# M12_Part_Left.net
KiCad netlist of a schematic drawn in Altium Designer
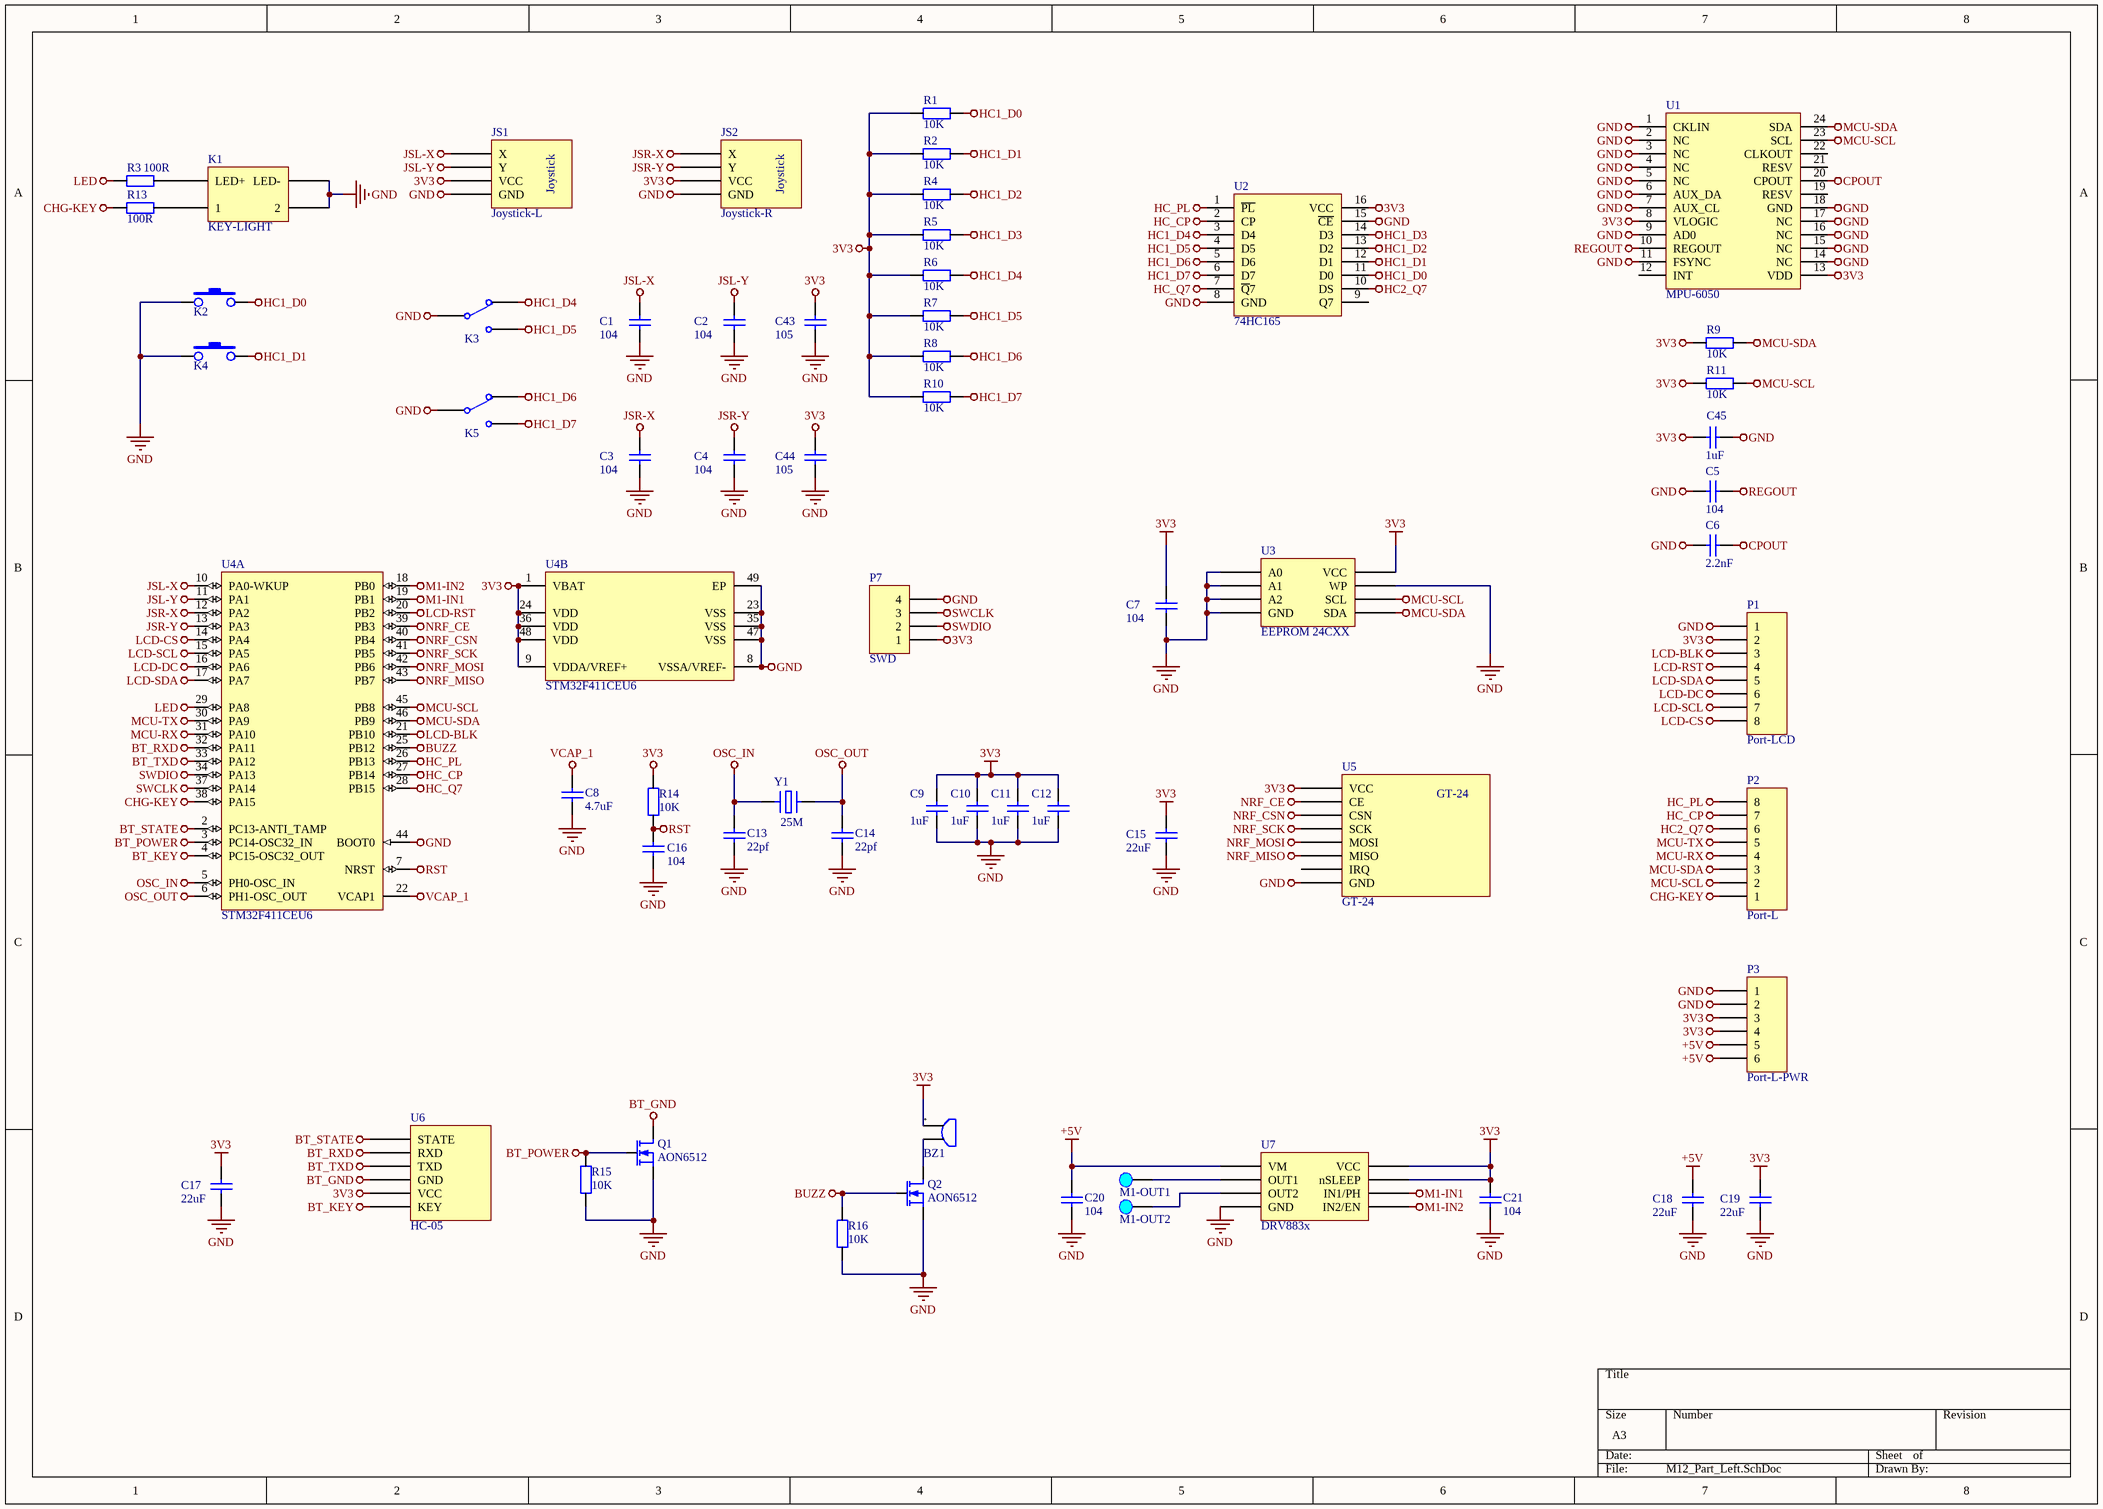
[diagram p0: M12_Part_Left.SchDoc]

(export (version "E")
  (design (tool "Eeschema 10.0.6"))
  (components
    (comp (ref "BZ1")
      (value "蜂鸣器")
      (footprint "BUZ-SMD_4P-L7.5-W7.5-P7.59-BR")
      (libsource (lib "元件库") (part "BZ"))
    )
    (comp (ref "C1")
      (value "104")
      (footprint "电容_C0603")
      (fields (field (name "C") "104"))
      (libsource (lib "元件库") (part "cap"))
    )
    (comp (ref "C2")
      (value "104")
      (footprint "电容_C0603")
      (fields (field (name "C") "104"))
      (libsource (lib "元件库") (part "cap"))
    )
    (comp (ref "C3")
      (value "104")
      (footprint "电容_C0603")
      (fields (field (name "C") "104"))
      (libsource (lib "元件库") (part "cap"))
    )
    (comp (ref "C4")
      (value "104")
      (footprint "电容_C0603")
      (fields (field (name "C") "104"))
      (libsource (lib "元件库") (part "cap"))
    )
    (comp (ref "C5")
      (value "104")
      (footprint "电容_C0603")
      (fields (field (name "C") "104"))
      (libsource (lib "元件库") (part "cap"))
    )
    (comp (ref "C6")
      (value "2.2nF")
      (footprint "电容_C0603")
      (fields (field (name "C") "2.2nF"))
      (libsource (lib "元件库") (part "cap"))
    )
    (comp (ref "C7")
      (value "104")
      (footprint "电容_C0603")
      (fields (field (name "C") "104"))
      (libsource (lib "元件库") (part "cap"))
    )
    (comp (ref "C8")
      (value "4.7uF")
      (footprint "电容_C0603")
      (fields (field (name "C") "4.7uF"))
      (libsource (lib "元件库") (part "cap"))
    )
    (comp (ref "C9")
      (value "1uF")
      (footprint "电容_C0603")
      (fields (field (name "C") "1uF"))
      (libsource (lib "元件库") (part "cap"))
    )
    (comp (ref "C10")
      (value "1uF")
      (footprint "电容_C0603")
      (fields (field (name "C") "1uF"))
      (libsource (lib "元件库") (part "cap"))
    )
    (comp (ref "C11")
      (value "1uF")
      (footprint "电容_C0603")
      (fields (field (name "C") "1uF"))
      (libsource (lib "元件库") (part "cap"))
    )
    (comp (ref "C12")
      (value "1uF")
      (footprint "电容_C0603")
      (fields (field (name "C") "1uF"))
      (libsource (lib "元件库") (part "cap"))
    )
    (comp (ref "C13")
      (value "22pf")
      (footprint "电容_C0603")
      (fields (field (name "C") "22pf"))
      (libsource (lib "元件库") (part "cap"))
    )
    (comp (ref "C14")
      (value "22pf")
      (footprint "电容_C0603")
      (fields (field (name "C") "22pf"))
      (libsource (lib "元件库") (part "cap"))
    )
    (comp (ref "C15")
      (value "22uF")
      (footprint "电容_C1206")
      (fields (field (name "C") "22uF"))
      (libsource (lib "元件库") (part "cap"))
    )
    (comp (ref "C16")
      (value "104")
      (footprint "电容_C0603")
      (fields (field (name "C") "104"))
      (libsource (lib "元件库") (part "cap"))
    )
    (comp (ref "C17")
      (value "22uF")
      (footprint "电容_C1206")
      (fields (field (name "C") "22uF"))
      (libsource (lib "元件库") (part "cap"))
    )
    (comp (ref "C18")
      (value "22uF")
      (footprint "电容_C1206")
      (fields (field (name "C") "22uF"))
      (libsource (lib "元件库") (part "cap"))
    )
    (comp (ref "C19")
      (value "22uF")
      (footprint "电容_C1206")
      (fields (field (name "C") "22uF"))
      (libsource (lib "元件库") (part "cap"))
    )
    (comp (ref "C20")
      (value "104")
      (footprint "电容_C0603")
      (fields (field (name "C") "104"))
      (libsource (lib "元件库") (part "cap"))
    )
    (comp (ref "C21")
      (value "104")
      (footprint "电容_C0603")
      (fields (field (name "C") "104"))
      (libsource (lib "元件库") (part "cap"))
    )
    (comp (ref "C43")
      (value "105")
      (footprint "电容_C0603")
      (fields (field (name "C") "105"))
      (libsource (lib "元件库") (part "cap"))
    )
    (comp (ref "C44")
      (value "105")
      (footprint "电容_C0603")
      (fields (field (name "C") "105"))
      (libsource (lib "元件库") (part "cap"))
    )
    (comp (ref "C45")
      (value "1uF")
      (footprint "电容_C0603")
      (fields (field (name "C") "1uF"))
      (libsource (lib "元件库") (part "cap"))
    )
    (comp (ref "JS1")
      (value "Joystick-L")
      (footprint "ZH1.5-LS-4P")
      (libsource (lib "xSchlib") (part "Joystick"))
    )
    (comp (ref "JS2")
      (value "Joystick-R")
      (footprint "ZH1.5-LS-4P")
      (libsource (lib "xSchlib") (part "Joystick"))
    )
    (comp (ref "K1")
      (value "KEY-LIGHT")
      (footprint "SW-TH_4P-L12.0-W12.0-P5.00-LS12.5")
      (libsource (lib "xSchlib") (part "KEY-LIGHT"))
    )
    (comp (ref "K2")
      (value "SKRP")
      (footprint "KEY-SMD_4P-L6.0-W6.0-P3.90-LS10.0")
      (libsource (lib "元件库") (part "SW-PB"))
    )
    (comp (ref "K3") (value "*") (footprint "ZH1.5-WS-3P") (libsource (lib "元件库") (part "KEY-3")))
    (comp (ref "K4")
      (value "SKRP")
      (footprint "KEY-SMD_4P-L6.0-W6.0-P3.90-LS10.0")
      (libsource (lib "元件库") (part "SW-PB"))
    )
    (comp (ref "K5") (value "*") (footprint "ZH1.5-WS-3P") (libsource (lib "元件库") (part "KEY-3")))
    (comp (ref "M1")
      (value "M1-OUT1")
      (footprint "Pad_B")
      (fields (field (name "_REMARKS") "M1-OUT1"))
      (libsource (lib "元件库") (part "Pad"))
    )
    (comp (ref "M2")
      (value "M1-OUT2")
      (footprint "Pad_B")
      (fields (field (name "_REMARKS") "M1-OUT2"))
      (libsource (lib "元件库") (part "Pad"))
    )
    (comp (ref "P1")
      (value "Port-LCD")
      (footprint "ZH1.5-LS-8P")
      (description "Header, 8-Pin")
      (fields (field (name "PUBLISHER") "Altium Limited"))
      (libsource (lib "") (part "Header 8_1"))
    )
    (comp (ref "P2")
      (value "Port-L")
      (footprint "ZH1.5-WS-8P")
      (description "Header, 8-Pin")
      (fields (field (name "PUBLISHER") "Altium Limited"))
      (libsource (lib "Miscellaneous Connectors") (part "Header 8"))
    )
    (comp (ref "P3")
      (value "Port-L-PWR")
      (footprint "ZH1.5-WS-6P")
      (description "Header, 6-Pin")
      (fields (field (name "PUBLISHER") "Altium Limited"))
      (libsource (lib "Miscellaneous Connectors") (part "Header 6"))
    )
    (comp (ref "P7")
      (value "SWD")
      (footprint "HDR1X4")
      (description "Header, 4-Pin")
      (fields (field (name "PUBLISHER") "Altium Limited"))
      (libsource (lib "Miscellaneous Connectors") (part "Header 4"))
    )
    (comp (ref "Q1") (value "AON6512") (footprint "MOS_SOT-23") (libsource (lib "元件库") (part "MOSFET-N")))
    (comp (ref "Q2") (value "AON6512") (footprint "MOS_SOT-23") (libsource (lib "元件库") (part "MOSFET-N")))
    (comp (ref "R1")
      (value "10K")
      (footprint "电阻_R0603")
      (fields (field (name "R") "10K"))
      (libsource (lib "元件库") (part "Res"))
    )
    (comp (ref "R2")
      (value "10K")
      (footprint "电阻_R0603")
      (fields (field (name "R") "10K"))
      (libsource (lib "元件库") (part "Res"))
    )
    (comp (ref "R3")
      (value "100R")
      (footprint "电阻_R0603")
      (fields (field (name "R") "100R"))
      (libsource (lib "元件库") (part "Res"))
    )
    (comp (ref "R4")
      (value "10K")
      (footprint "电阻_R0603")
      (fields (field (name "R") "10K"))
      (libsource (lib "元件库") (part "Res"))
    )
    (comp (ref "R5")
      (value "10K")
      (footprint "电阻_R0603")
      (fields (field (name "R") "10K"))
      (libsource (lib "元件库") (part "Res"))
    )
    (comp (ref "R6")
      (value "10K")
      (footprint "电阻_R0603")
      (fields (field (name "R") "10K"))
      (libsource (lib "元件库") (part "Res"))
    )
    (comp (ref "R7")
      (value "10K")
      (footprint "电阻_R0603")
      (fields (field (name "R") "10K"))
      (libsource (lib "元件库") (part "Res"))
    )
    (comp (ref "R8")
      (value "10K")
      (footprint "电阻_R0603")
      (fields (field (name "R") "10K"))
      (libsource (lib "元件库") (part "Res"))
    )
    (comp (ref "R9")
      (value "10K")
      (footprint "电阻_R0603")
      (fields (field (name "R") "10K"))
      (libsource (lib "") (part "Res_1"))
    )
    (comp (ref "R10")
      (value "10K")
      (footprint "电阻_R0603")
      (fields (field (name "R") "10K"))
      (libsource (lib "元件库") (part "Res"))
    )
    (comp (ref "R11")
      (value "10K")
      (footprint "电阻_R0603")
      (fields (field (name "R") "10K"))
      (libsource (lib "") (part "Res_1"))
    )
    (comp (ref "R13")
      (value "100R")
      (footprint "电阻_R0603")
      (fields (field (name "R") "100R"))
      (libsource (lib "元件库") (part "Res"))
    )
    (comp (ref "R14")
      (value "10K")
      (footprint "电阻_R0603")
      (fields (field (name "R") "10K"))
      (libsource (lib "") (part "Res_2"))
    )
    (comp (ref "R15")
      (value "10K")
      (footprint "电阻_R0603")
      (fields (field (name "R") "10K"))
      (libsource (lib "") (part "Res_2"))
    )
    (comp (ref "R16")
      (value "10K")
      (footprint "电阻_R0603")
      (fields (field (name "R") "10K"))
      (libsource (lib "") (part "Res_2"))
    )
    (comp (ref "U1") (value "MPU-6050") (footprint "陀螺仪_QFN24") (libsource (lib "元件库") (part "MPU-6050")))
    (comp (ref "U2") (value "74HC165") (footprint "74HC系列_SOP16") (libsource (lib "元件库") (part "74HC165")))
    (comp (ref "U3")
      (value "EEPROM 24CXX")
      (footprint "SOP8")
      (description "24CXX")
      (libsource (lib "xSchlib") (part "EEPROM 24CXX"))
    )
    (comp (ref "U4")
      (value "STM32F411CEU6")
      (footprint "STM-UFQFPN48_N")
      (fields (field (name "MANUFACTURER") "STMicroelectronics") (field (name "PARTNUMBER") "STM32F401CCU6"))
      (libsource (lib "STMicroelectronics STM32 F4") (part "STM32F401CCU6"))
    )
    (comp (ref "U5")
      (value "GT-24")
      (footprint "GT-24")
      (description "NRF24L01")
      (libsource (lib "xSchlib") (part "GT-24"))
    )
    (comp (ref "U6")
      (value "HC-05")
      (footprint "HDR1X6")
      (description "Bluetooth")
      (libsource (lib "xSchLib") (part "HC-05"))
    )
    (comp (ref "U7")
      (value "DRV883x")
      (footprint "WSON-8_L2.0-W2.0-P0.50-TL-EP")
      (libsource (lib "xSchlib") (part "DRV883x"))
    )
    (comp (ref "Y1")
      (value "XTAL")
      (footprint "晶振_3225")
      (fields (field (name "F") "25M"))
      (libsource (lib "元件库") (part "XTAL"))
    )
  )
  (nets
    (net (code "1") (name "+5V") (class "Default")
      (node (ref "C18") (pin "2") (pinfunction "2_2") (pintype "passive"))
      (node (ref "C20") (pin "1") (pinfunction "1_1") (pintype "passive"))
      (node (ref "P3") (pin "5") (pinfunction "5_5") (pintype "passive"))
      (node (ref "P3") (pin "6") (pinfunction "6_6") (pintype "passive"))
      (node (ref "U7") (pin "1") (pinfunction "VM_1") (pintype "passive"))
    )
    (net (code "2") (name "3V3") (class "Default")
      (node (ref "BZ1") (pin "1") (pinfunction "1_1") (pintype "passive"))
      (node (ref "C10") (pin "2") (pinfunction "2_2") (pintype "passive"))
      (node (ref "C11") (pin "2") (pinfunction "2_2") (pintype "passive"))
      (node (ref "C12") (pin "2") (pinfunction "2_2") (pintype "passive"))
      (node (ref "C15") (pin "2") (pinfunction "2_2") (pintype "passive"))
      (node (ref "C17") (pin "2") (pinfunction "2_2") (pintype "passive"))
      (node (ref "C19") (pin "2") (pinfunction "2_2") (pintype "passive"))
      (node (ref "C21") (pin "2") (pinfunction "2_2") (pintype "passive"))
      (node (ref "C43") (pin "2") (pinfunction "2_2") (pintype "passive"))
      (node (ref "C44") (pin "2") (pinfunction "2_2") (pintype "passive"))
      (node (ref "C45") (pin "2") (pinfunction "2_2") (pintype "passive"))
      (node (ref "C7") (pin "2") (pinfunction "2_2") (pintype "passive"))
      (node (ref "C9") (pin "2") (pinfunction "2_2") (pintype "passive"))
      (node (ref "JS1") (pin "2") (pinfunction "VCC_2") (pintype "passive"))
      (node (ref "JS2") (pin "2") (pinfunction "VCC_2") (pintype "passive"))
      (node (ref "P1") (pin "2") (pinfunction "2_2") (pintype "passive"))
      (node (ref "P3") (pin "3") (pinfunction "3_3") (pintype "passive"))
      (node (ref "P3") (pin "4") (pinfunction "4_4") (pintype "passive"))
      (node (ref "P7") (pin "1") (pinfunction "1_1") (pintype "passive"))
      (node (ref "R1") (pin "1") (pinfunction "1_1") (pintype "passive"))
      (node (ref "R10") (pin "1") (pinfunction "1_1") (pintype "passive"))
      (node (ref "R11") (pin "2") (pinfunction "2_2") (pintype "passive"))
      (node (ref "R14") (pin "2") (pinfunction "2_2") (pintype "passive"))
      (node (ref "R2") (pin "1") (pinfunction "1_1") (pintype "passive"))
      (node (ref "R4") (pin "1") (pinfunction "1_1") (pintype "passive"))
      (node (ref "R5") (pin "1") (pinfunction "1_1") (pintype "passive"))
      (node (ref "R6") (pin "1") (pinfunction "1_1") (pintype "passive"))
      (node (ref "R7") (pin "1") (pinfunction "1_1") (pintype "passive"))
      (node (ref "R8") (pin "1") (pinfunction "1_1") (pintype "passive"))
      (node (ref "R9") (pin "2") (pinfunction "2_2") (pintype "passive"))
      (node (ref "U1") (pin "13") (pinfunction "VDD_13") (pintype "passive"))
      (node (ref "U1") (pin "8") (pinfunction "VLOGIC_8") (pintype "passive"))
      (node (ref "U2") (pin "16") (pinfunction "VCC_16") (pintype "passive"))
      (node (ref "U3") (pin "8") (pinfunction "VCC_8") (pintype "passive"))
      (node (ref "U4") (pin "1") (pinfunction "VBAT_1") (pintype "power_in"))
      (node (ref "U4") (pin "24") (pinfunction "VDD_24") (pintype "power_in"))
      (node (ref "U4") (pin "36") (pinfunction "VDD_36") (pintype "power_in"))
      (node (ref "U4") (pin "48") (pinfunction "VDD_48") (pintype "power_in"))
      (node (ref "U4") (pin "9") (pinfunction "VDDA/VREF+_9") (pintype "power_in"))
      (node (ref "U5") (pin "1") (pinfunction "VCC_1") (pintype "passive"))
      (node (ref "U6") (pin "2") (pinfunction "VCC_2") (pintype "passive"))
      (node (ref "U7") (pin "7") (pinfunction "nSLEEP_7") (pintype "passive"))
      (node (ref "U7") (pin "8") (pinfunction "VCC_8") (pintype "passive"))
    )
    (net (code "3") (name "BT_GND") (class "Default")
      (node (ref "Q1") (pin "2") (pinfunction "D_2") (pintype "passive"))
      (node (ref "U6") (pin "3") (pinfunction "GND_3") (pintype "passive"))
    )
    (net (code "4") (name "BT_KEY") (class "Default")
      (node (ref "U4") (pin "4") (pinfunction "PC15-OSC32_OUT_4") (pintype "bidirectional"))
      (node (ref "U6") (pin "1") (pinfunction "KEY_1") (pintype "passive"))
    )
    (net (code "5") (name "BT_POWER") (class "Default")
      (node (ref "Q1") (pin "1") (pinfunction "G_1") (pintype "passive"))
      (node (ref "R15") (pin "2") (pinfunction "2_2") (pintype "passive"))
      (node (ref "U4") (pin "3") (pinfunction "PC14-OSC32_IN_3") (pintype "bidirectional"))
    )
    (net (code "6") (name "BT_RXD") (class "Default")
      (node (ref "U4") (pin "32") (pinfunction "PA11_32") (pintype "bidirectional"))
      (node (ref "U6") (pin "5") (pinfunction "RXD_5") (pintype "passive"))
    )
    (net (code "7") (name "BT_STATE") (class "Default")
      (node (ref "U4") (pin "2") (pinfunction "PC13-ANTI_TAMP_2") (pintype "bidirectional"))
      (node (ref "U6") (pin "6") (pinfunction "STATE_6") (pintype "passive"))
    )
    (net (code "8") (name "BT_TXD") (class "Default")
      (node (ref "U4") (pin "33") (pinfunction "PA12_33") (pintype "bidirectional"))
      (node (ref "U6") (pin "4") (pinfunction "TXD_4") (pintype "passive"))
    )
    (net (code "9") (name "BUZZ") (class "Default")
      (node (ref "Q2") (pin "1") (pinfunction "G_1") (pintype "passive"))
      (node (ref "R16") (pin "2") (pinfunction "2_2") (pintype "passive"))
      (node (ref "U4") (pin "25") (pinfunction "PB12_25") (pintype "bidirectional"))
    )
    (net (code "10") (name "CHG-KEY") (class "Default")
      (node (ref "P2") (pin "1") (pinfunction "1_1") (pintype "passive"))
      (node (ref "R13") (pin "1") (pinfunction "1_1") (pintype "passive"))
      (node (ref "U4") (pin "38") (pinfunction "PA15_38") (pintype "bidirectional"))
    )
    (net (code "11") (name "CPOUT") (class "Default")
      (node (ref "C6") (pin "1") (pinfunction "1_1") (pintype "passive"))
      (node (ref "U1") (pin "20") (pinfunction "CPOUT_20") (pintype "passive"))
    )
    (net (code "12") (name "GND") (class "Default")
      (node (ref "C1") (pin "1") (pinfunction "1_1") (pintype "passive"))
      (node (ref "C10") (pin "1") (pinfunction "1_1") (pintype "passive"))
      (node (ref "C11") (pin "1") (pinfunction "1_1") (pintype "passive"))
      (node (ref "C12") (pin "1") (pinfunction "1_1") (pintype "passive"))
      (node (ref "C13") (pin "2") (pinfunction "2_2") (pintype "passive"))
      (node (ref "C14") (pin "2") (pinfunction "2_2") (pintype "passive"))
      (node (ref "C15") (pin "1") (pinfunction "1_1") (pintype "passive"))
      (node (ref "C16") (pin "1") (pinfunction "1_1") (pintype "passive"))
      (node (ref "C17") (pin "1") (pinfunction "1_1") (pintype "passive"))
      (node (ref "C18") (pin "1") (pinfunction "1_1") (pintype "passive"))
      (node (ref "C19") (pin "1") (pinfunction "1_1") (pintype "passive"))
      (node (ref "C2") (pin "1") (pinfunction "1_1") (pintype "passive"))
      (node (ref "C20") (pin "2") (pinfunction "2_2") (pintype "passive"))
      (node (ref "C21") (pin "1") (pinfunction "1_1") (pintype "passive"))
      (node (ref "C3") (pin "1") (pinfunction "1_1") (pintype "passive"))
      (node (ref "C4") (pin "1") (pinfunction "1_1") (pintype "passive"))
      (node (ref "C43") (pin "1") (pinfunction "1_1") (pintype "passive"))
      (node (ref "C44") (pin "1") (pinfunction "1_1") (pintype "passive"))
      (node (ref "C45") (pin "1") (pinfunction "1_1") (pintype "passive"))
      (node (ref "C5") (pin "2") (pinfunction "2_2") (pintype "passive"))
      (node (ref "C6") (pin "2") (pinfunction "2_2") (pintype "passive"))
      (node (ref "C7") (pin "1") (pinfunction "1_1") (pintype "passive"))
      (node (ref "C8") (pin "1") (pinfunction "1_1") (pintype "passive"))
      (node (ref "C9") (pin "1") (pinfunction "1_1") (pintype "passive"))
      (node (ref "JS1") (pin "1") (pinfunction "GND_1") (pintype "passive"))
      (node (ref "JS2") (pin "1") (pinfunction "GND_1") (pintype "passive"))
      (node (ref "K1") (pin "2") (pinfunction "2_2") (pintype "passive"))
      (node (ref "K1") (pin "4") (pinfunction "LED-_4") (pintype "passive"))
      (node (ref "K2") (pin "1") (pinfunction "1_1") (pintype "passive"))
      (node (ref "K3") (pin "1") (pinfunction "1_1") (pintype "passive"))
      (node (ref "K4") (pin "1") (pinfunction "1_1") (pintype "passive"))
      (node (ref "K5") (pin "1") (pinfunction "1_1") (pintype "passive"))
      (node (ref "P1") (pin "1") (pinfunction "1_1") (pintype "passive"))
      (node (ref "P3") (pin "1") (pinfunction "1_1") (pintype "passive"))
      (node (ref "P3") (pin "2") (pinfunction "2_2") (pintype "passive"))
      (node (ref "P7") (pin "4") (pinfunction "4_4") (pintype "passive"))
      (node (ref "Q1") (pin "3") (pinfunction "S_3") (pintype "passive"))
      (node (ref "Q2") (pin "3") (pinfunction "S_3") (pintype "passive"))
      (node (ref "R15") (pin "1") (pinfunction "1_1") (pintype "passive"))
      (node (ref "R16") (pin "1") (pinfunction "1_1") (pintype "passive"))
      (node (ref "U1") (pin "1") (pinfunction "CKLIN_1") (pintype "passive"))
      (node (ref "U1") (pin "11") (pinfunction "FSYNC_11") (pintype "passive"))
      (node (ref "U1") (pin "14") (pinfunction "NC_14") (pintype "passive"))
      (node (ref "U1") (pin "15") (pinfunction "NC_15") (pintype "passive"))
      (node (ref "U1") (pin "16") (pinfunction "NC_16") (pintype "passive"))
      (node (ref "U1") (pin "17") (pinfunction "NC_17") (pintype "passive"))
      (node (ref "U1") (pin "18") (pinfunction "GND_18") (pintype "passive"))
      (node (ref "U1") (pin "2") (pinfunction "NC_2") (pintype "passive"))
      (node (ref "U1") (pin "3") (pinfunction "NC_3") (pintype "passive"))
      (node (ref "U1") (pin "4") (pinfunction "NC_4") (pintype "passive"))
      (node (ref "U1") (pin "5") (pinfunction "NC_5") (pintype "passive"))
      (node (ref "U1") (pin "6") (pinfunction "AUX_DA_6") (pintype "passive"))
      (node (ref "U1") (pin "7") (pinfunction "AUX_CL_7") (pintype "passive"))
      (node (ref "U1") (pin "9") (pinfunction "AD0_9") (pintype "passive"))
      (node (ref "U2") (pin "15") (pinfunction "~{CE}_15") (pintype "passive"))
      (node (ref "U2") (pin "8") (pinfunction "GND_8") (pintype "passive"))
      (node (ref "U3") (pin "1") (pinfunction "A0_1") (pintype "passive"))
      (node (ref "U3") (pin "2") (pinfunction "A1_2") (pintype "passive"))
      (node (ref "U3") (pin "3") (pinfunction "A2_3") (pintype "passive"))
      (node (ref "U3") (pin "4") (pinfunction "GND_4") (pintype "passive"))
      (node (ref "U3") (pin "7") (pinfunction "WP_7") (pintype "passive"))
      (node (ref "U4") (pin "23") (pinfunction "VSS_23") (pintype "power_in"))
      (node (ref "U4") (pin "35") (pinfunction "VSS_35") (pintype "power_in"))
      (node (ref "U4") (pin "44") (pinfunction "BOOT0_44") (pintype "input"))
      (node (ref "U4") (pin "47") (pinfunction "VSS_47") (pintype "power_in"))
      (node (ref "U4") (pin "49") (pinfunction "EP_49") (pintype "power_in"))
      (node (ref "U4") (pin "8") (pinfunction "VSSA/VREF-_8") (pintype "power_in"))
      (node (ref "U5") (pin "8") (pinfunction "GND_8") (pintype "passive"))
      (node (ref "U7") (pin "4") (pinfunction "GND_4") (pintype "passive"))
    )
    (net (code "13") (name "HC1_D0") (class "Default")
      (node (ref "K2") (pin "2") (pinfunction "2_2") (pintype "passive"))
      (node (ref "R1") (pin "2") (pinfunction "2_2") (pintype "passive"))
      (node (ref "U2") (pin "11") (pinfunction "D0_11") (pintype "passive"))
    )
    (net (code "14") (name "HC1_D1") (class "Default")
      (node (ref "K4") (pin "2") (pinfunction "2_2") (pintype "passive"))
      (node (ref "R2") (pin "2") (pinfunction "2_2") (pintype "passive"))
      (node (ref "U2") (pin "12") (pinfunction "D1_12") (pintype "passive"))
    )
    (net (code "15") (name "HC1_D2") (class "Default")
      (node (ref "R4") (pin "2") (pinfunction "2_2") (pintype "passive"))
      (node (ref "U2") (pin "13") (pinfunction "D2_13") (pintype "passive"))
    )
    (net (code "16") (name "HC1_D3") (class "Default")
      (node (ref "R5") (pin "2") (pinfunction "2_2") (pintype "passive"))
      (node (ref "U2") (pin "14") (pinfunction "D3_14") (pintype "passive"))
    )
    (net (code "17") (name "HC1_D4") (class "Default")
      (node (ref "K3") (pin "2") (pinfunction "2_2") (pintype "passive"))
      (node (ref "R6") (pin "2") (pinfunction "2_2") (pintype "passive"))
      (node (ref "U2") (pin "3") (pinfunction "D4_3") (pintype "passive"))
    )
    (net (code "18") (name "HC1_D5") (class "Default")
      (node (ref "K3") (pin "3") (pinfunction "3_3") (pintype "passive"))
      (node (ref "R7") (pin "2") (pinfunction "2_2") (pintype "passive"))
      (node (ref "U2") (pin "4") (pinfunction "D5_4") (pintype "passive"))
    )
    (net (code "19") (name "HC1_D6") (class "Default")
      (node (ref "K5") (pin "2") (pinfunction "2_2") (pintype "passive"))
      (node (ref "R8") (pin "2") (pinfunction "2_2") (pintype "passive"))
      (node (ref "U2") (pin "5") (pinfunction "D6_5") (pintype "passive"))
    )
    (net (code "20") (name "HC1_D7") (class "Default")
      (node (ref "K5") (pin "3") (pinfunction "3_3") (pintype "passive"))
      (node (ref "R10") (pin "2") (pinfunction "2_2") (pintype "passive"))
      (node (ref "U2") (pin "6") (pinfunction "D7_6") (pintype "passive"))
    )
    (net (code "21") (name "HC2_Q7") (class "Default")
      (node (ref "P2") (pin "6") (pinfunction "6_6") (pintype "passive"))
      (node (ref "U2") (pin "10") (pinfunction "DS_10") (pintype "passive"))
    )
    (net (code "22") (name "HC_CP") (class "Default")
      (node (ref "P2") (pin "7") (pinfunction "7_7") (pintype "passive"))
      (node (ref "U2") (pin "2") (pinfunction "CP_2") (pintype "passive"))
      (node (ref "U4") (pin "27") (pinfunction "PB14_27") (pintype "bidirectional"))
    )
    (net (code "23") (name "HC_PL") (class "Default")
      (node (ref "P2") (pin "8") (pinfunction "8_8") (pintype "passive"))
      (node (ref "U2") (pin "1") (pinfunction "~{PL}_1") (pintype "passive"))
      (node (ref "U4") (pin "26") (pinfunction "PB13_26") (pintype "bidirectional"))
    )
    (net (code "24") (name "HC_Q7") (class "Default")
      (node (ref "U2") (pin "7") (pinfunction "~{Q}7_7") (pintype "passive"))
      (node (ref "U4") (pin "28") (pinfunction "PB15_28") (pintype "bidirectional"))
    )
    (net (code "25") (name "JSL-X") (class "Default")
      (node (ref "C1") (pin "2") (pinfunction "2_2") (pintype "passive"))
      (node (ref "JS1") (pin "4") (pinfunction "X_4") (pintype "passive"))
      (node (ref "U4") (pin "10") (pinfunction "PA0-WKUP_10") (pintype "bidirectional"))
    )
    (net (code "26") (name "JSL-Y") (class "Default")
      (node (ref "C2") (pin "2") (pinfunction "2_2") (pintype "passive"))
      (node (ref "JS1") (pin "3") (pinfunction "Y_3") (pintype "passive"))
      (node (ref "U4") (pin "11") (pinfunction "PA1_11") (pintype "bidirectional"))
    )
    (net (code "27") (name "JSR-X") (class "Default")
      (node (ref "C3") (pin "2") (pinfunction "2_2") (pintype "passive"))
      (node (ref "JS2") (pin "4") (pinfunction "X_4") (pintype "passive"))
      (node (ref "U4") (pin "12") (pinfunction "PA2_12") (pintype "bidirectional"))
    )
    (net (code "28") (name "JSR-Y") (class "Default")
      (node (ref "C4") (pin "2") (pinfunction "2_2") (pintype "passive"))
      (node (ref "JS2") (pin "3") (pinfunction "Y_3") (pintype "passive"))
      (node (ref "U4") (pin "13") (pinfunction "PA3_13") (pintype "bidirectional"))
    )
    (net (code "29") (name "LCD-BLK") (class "Default")
      (node (ref "P1") (pin "3") (pinfunction "3_3") (pintype "passive"))
      (node (ref "U4") (pin "21") (pinfunction "PB10_21") (pintype "bidirectional"))
    )
    (net (code "30") (name "LCD-CS") (class "Default")
      (node (ref "P1") (pin "8") (pinfunction "8_8") (pintype "passive"))
      (node (ref "U4") (pin "14") (pinfunction "PA4_14") (pintype "bidirectional"))
    )
    (net (code "31") (name "LCD-DC") (class "Default")
      (node (ref "P1") (pin "6") (pinfunction "6_6") (pintype "passive"))
      (node (ref "U4") (pin "16") (pinfunction "PA6_16") (pintype "bidirectional"))
    )
    (net (code "32") (name "LCD-RST") (class "Default")
      (node (ref "P1") (pin "4") (pinfunction "4_4") (pintype "passive"))
      (node (ref "U4") (pin "20") (pinfunction "PB2_20") (pintype "bidirectional"))
    )
    (net (code "33") (name "LCD-SCL") (class "Default")
      (node (ref "P1") (pin "7") (pinfunction "7_7") (pintype "passive"))
      (node (ref "U4") (pin "15") (pinfunction "PA5_15") (pintype "bidirectional"))
    )
    (net (code "34") (name "LCD-SDA") (class "Default")
      (node (ref "P1") (pin "5") (pinfunction "5_5") (pintype "passive"))
      (node (ref "U4") (pin "17") (pinfunction "PA7_17") (pintype "bidirectional"))
    )
    (net (code "35") (name "LED") (class "Default")
      (node (ref "R3") (pin "1") (pinfunction "1_1") (pintype "passive"))
      (node (ref "U4") (pin "29") (pinfunction "PA8_29") (pintype "bidirectional"))
    )
    (net (code "36") (name "M1-IN1") (class "Default")
      (node (ref "U4") (pin "19") (pinfunction "PB1_19") (pintype "bidirectional"))
      (node (ref "U7") (pin "6") (pinfunction "IN1/PH_6") (pintype "passive"))
    )
    (net (code "37") (name "M1-IN2") (class "Default")
      (node (ref "U4") (pin "18") (pinfunction "PB0_18") (pintype "bidirectional"))
      (node (ref "U7") (pin "5") (pinfunction "IN2/EN_5") (pintype "passive"))
    )
    (net (code "38") (name "MCU-RX") (class "Default")
      (node (ref "P2") (pin "4") (pinfunction "4_4") (pintype "passive"))
      (node (ref "U4") (pin "31") (pinfunction "PA10_31") (pintype "bidirectional"))
    )
    (net (code "39") (name "MCU-SCL") (class "Default")
      (node (ref "P2") (pin "2") (pinfunction "2_2") (pintype "passive"))
      (node (ref "R11") (pin "1") (pinfunction "1_1") (pintype "passive"))
      (node (ref "U1") (pin "23") (pinfunction "SCL_23") (pintype "passive"))
      (node (ref "U3") (pin "6") (pinfunction "SCL_6") (pintype "passive"))
      (node (ref "U4") (pin "45") (pinfunction "PB8_45") (pintype "bidirectional"))
    )
    (net (code "40") (name "MCU-SDA") (class "Default")
      (node (ref "P2") (pin "3") (pinfunction "3_3") (pintype "passive"))
      (node (ref "R9") (pin "1") (pinfunction "1_1") (pintype "passive"))
      (node (ref "U1") (pin "24") (pinfunction "SDA_24") (pintype "passive"))
      (node (ref "U3") (pin "5") (pinfunction "SDA_5") (pintype "passive"))
      (node (ref "U4") (pin "46") (pinfunction "PB9_46") (pintype "bidirectional"))
    )
    (net (code "41") (name "MCU-TX") (class "Default")
      (node (ref "P2") (pin "5") (pinfunction "5_5") (pintype "passive"))
      (node (ref "U4") (pin "30") (pinfunction "PA9_30") (pintype "bidirectional"))
    )
    (net (code "42") (name "NRF_CE") (class "Default")
      (node (ref "U4") (pin "39") (pinfunction "PB3_39") (pintype "bidirectional"))
      (node (ref "U5") (pin "2") (pinfunction "CE_2") (pintype "passive"))
    )
    (net (code "43") (name "NRF_CSN") (class "Default")
      (node (ref "U4") (pin "40") (pinfunction "PB4_40") (pintype "bidirectional"))
      (node (ref "U5") (pin "3") (pinfunction "CSN_3") (pintype "passive"))
    )
    (net (code "44") (name "NRF_MISO") (class "Default")
      (node (ref "U4") (pin "43") (pinfunction "PB7_43") (pintype "bidirectional"))
      (node (ref "U5") (pin "6") (pinfunction "MISO_6") (pintype "passive"))
    )
    (net (code "45") (name "NRF_MOSI") (class "Default")
      (node (ref "U4") (pin "42") (pinfunction "PB6_42") (pintype "bidirectional"))
      (node (ref "U5") (pin "5") (pinfunction "MOSI_5") (pintype "passive"))
    )
    (net (code "46") (name "NRF_SCK") (class "Default")
      (node (ref "U4") (pin "41") (pinfunction "PB5_41") (pintype "bidirectional"))
      (node (ref "U5") (pin "4") (pinfunction "SCK_4") (pintype "passive"))
    )
    (net (code "47") (name "Net-(K1-LED+)") (class "Default")
      (node (ref "K1") (pin "3") (pinfunction "LED+_3") (pintype "passive"))
      (node (ref "R3") (pin "2") (pinfunction "2_2") (pintype "passive"))
    )
    (net (code "48") (name "Net-(K1-Pad1)") (class "Default")
      (node (ref "K1") (pin "1") (pinfunction "1_1") (pintype "passive"))
      (node (ref "R13") (pin "2") (pinfunction "2_2") (pintype "passive"))
    )
    (net (code "49") (name "Net-(M1-*)") (class "Default")
      (node (ref "M1") (pin "1") (pinfunction "*_1") (pintype "passive"))
      (node (ref "U7") (pin "2") (pinfunction "OUT1_2") (pintype "passive"))
    )
    (net (code "50") (name "Net-(M2-*)") (class "Default")
      (node (ref "M2") (pin "1") (pinfunction "*_1") (pintype "passive"))
      (node (ref "U7") (pin "3") (pinfunction "OUT2_3") (pintype "passive"))
    )
    (net (code "51") (name "Net-(Q2-D)") (class "Default")
      (node (ref "BZ1") (pin "2") (pinfunction "2_2") (pintype "passive"))
      (node (ref "Q2") (pin "2") (pinfunction "D_2") (pintype "passive"))
    )
    (net (code "52") (name "OSC_IN") (class "Default")
      (node (ref "C13") (pin "1") (pinfunction "1_1") (pintype "passive"))
      (node (ref "U4") (pin "5") (pinfunction "PH0-OSC_IN_5") (pintype "bidirectional"))
      (node (ref "Y1") (pin "1") (pinfunction "1_1") (pintype "passive"))
    )
    (net (code "53") (name "OSC_OUT") (class "Default")
      (node (ref "C14") (pin "1") (pinfunction "1_1") (pintype "passive"))
      (node (ref "U4") (pin "6") (pinfunction "PH1-OSC_OUT_6") (pintype "bidirectional"))
      (node (ref "Y1") (pin "2") (pinfunction "2_2") (pintype "passive"))
    )
    (net (code "54") (name "REGOUT") (class "Default")
      (node (ref "C5") (pin "1") (pinfunction "1_1") (pintype "passive"))
      (node (ref "U1") (pin "10") (pinfunction "REGOUT_10") (pintype "passive"))
    )
    (net (code "55") (name "RST") (class "Default")
      (node (ref "C16") (pin "2") (pinfunction "2_2") (pintype "passive"))
      (node (ref "R14") (pin "1") (pinfunction "1_1") (pintype "passive"))
      (node (ref "U4") (pin "7") (pinfunction "NRST_7") (pintype "bidirectional"))
    )
    (net (code "56") (name "SWCLK") (class "Default")
      (node (ref "P7") (pin "3") (pinfunction "3_3") (pintype "passive"))
      (node (ref "U4") (pin "37") (pinfunction "PA14_37") (pintype "bidirectional"))
    )
    (net (code "57") (name "SWDIO") (class "Default")
      (node (ref "P7") (pin "2") (pinfunction "2_2") (pintype "passive"))
      (node (ref "U4") (pin "34") (pinfunction "PA13_34") (pintype "bidirectional"))
    )
    (net (code "58") (name "VCAP_1") (class "Default")
      (node (ref "C8") (pin "2") (pinfunction "2_2") (pintype "passive"))
      (node (ref "U4") (pin "22") (pinfunction "VCAP1_22") (pintype "power_in"))
    )
    (net (code "59") (name "unconnected-(U1-CLKOUT-Pad22)") (class "Default")
      (node (ref "U1") (pin "22") (pinfunction "CLKOUT_22") (pintype "passive"))
    )
    (net (code "60") (name "unconnected-(U1-INT-Pad12)") (class "Default")
      (node (ref "U1") (pin "12") (pinfunction "INT_12") (pintype "passive"))
    )
    (net (code "61") (name "unconnected-(U1-Pad0)") (class "Default")
      (node (ref "U1") (pin "0") (pintype "passive"))
    )
    (net (code "62") (name "unconnected-(U1-RESV-Pad19)") (class "Default")
      (node (ref "U1") (pin "19") (pinfunction "RESV_19") (pintype "passive"))
    )
    (net (code "63") (name "unconnected-(U1-RESV-Pad21)") (class "Default")
      (node (ref "U1") (pin "21") (pinfunction "RESV_21") (pintype "passive"))
    )
    (net (code "64") (name "unconnected-(U2-Q7-Pad9)") (class "Default")
      (node (ref "U2") (pin "9") (pinfunction "Q7_9") (pintype "passive"))
    )
    (net (code "65") (name "unconnected-(U5-IRQ-Pad7)") (class "Default")
      (node (ref "U5") (pin "7") (pinfunction "IRQ_7") (pintype "passive"))
    )
  )
)
